# Power_Supply_and_Buttons.net
KiCad netlist of a schematic drawn in Altium Designer
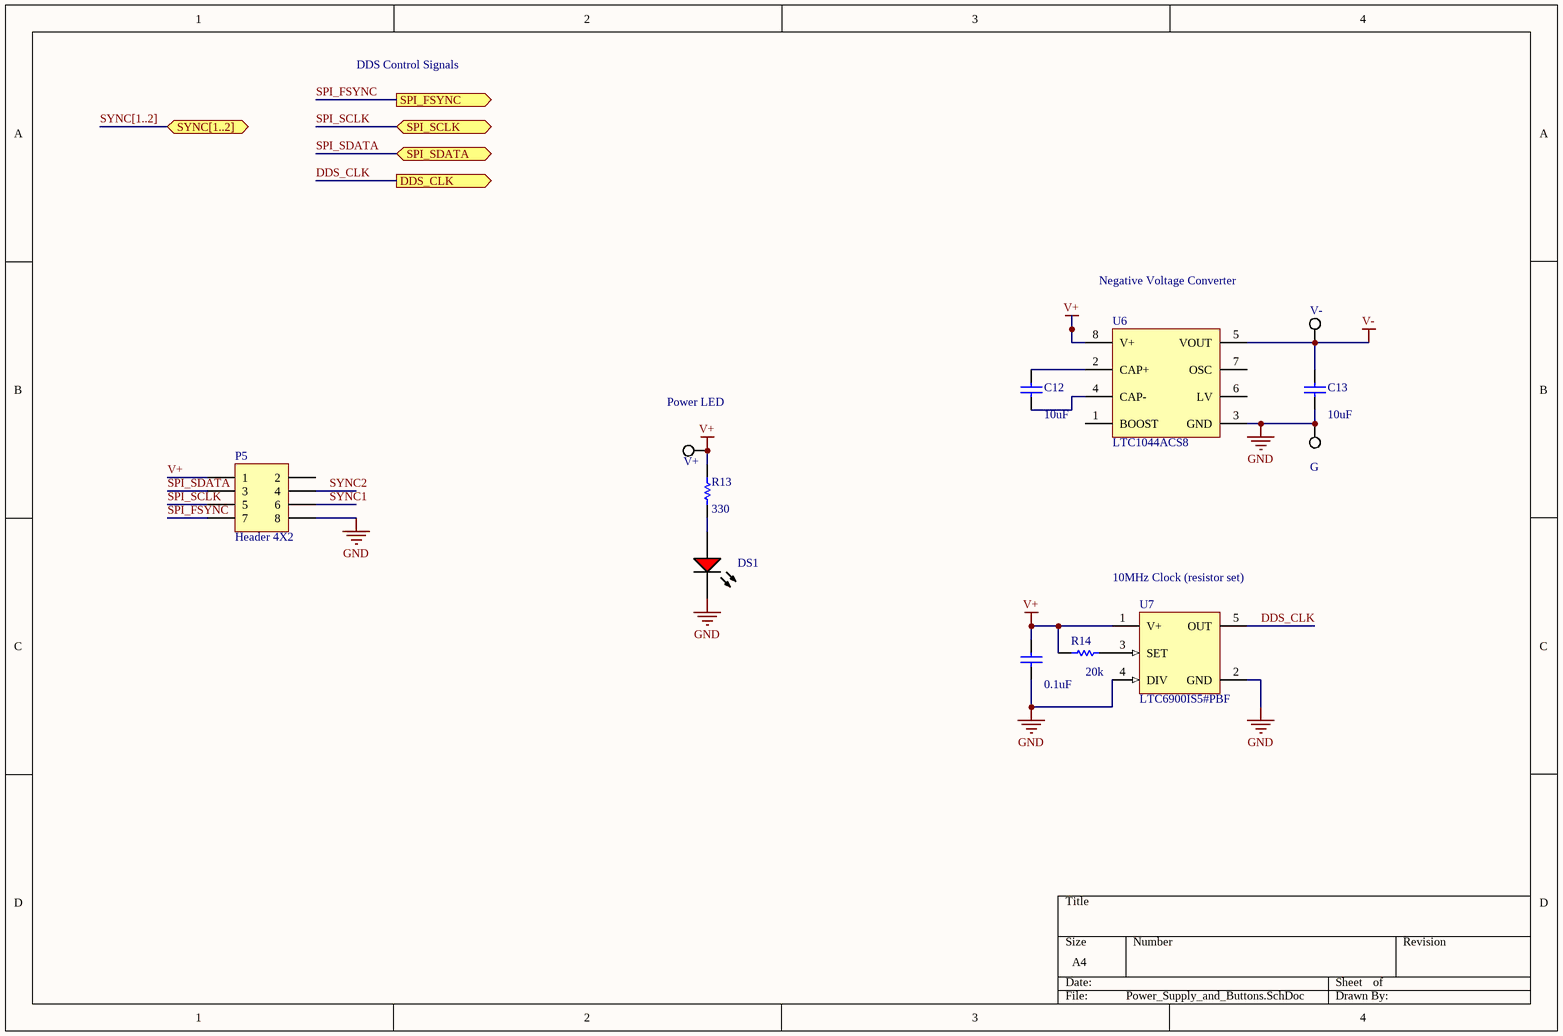
[diagram p0: Power_Supply_and_Buttons.SchDoc]

(export (version "E")
  (design (tool "Eeschema 10.0.6"))
  (components
    (comp (ref "C12")
      (value "10uF")
      (footprint "1608[0603]")
      (description "Capacitor (Semiconductor SIM Model)")
      (fields (field (name "PUBLISHER") "Altium Limited"))
      (libsource (lib "Miscellaneous Devices") (part "Cap Semi"))
    )
    (comp (ref "C13")
      (value "10uF")
      (footprint "1608[0603]")
      (description "Capacitor (Semiconductor SIM Model)")
      (fields (field (name "PUBLISHER") "Altium Limited"))
      (libsource (lib "Miscellaneous Devices") (part "Cap Semi"))
    )
    (comp (ref "C14")
      (value "0.1uF")
      (footprint "1608[0603]")
      (description "Capacitor (Semiconductor SIM Model)")
      (fields (field (name "PUBLISHER") "Altium Limited"))
      (libsource (lib "Miscellaneous Devices") (part "Cap Semi"))
    )
    (comp (ref "DS1")
      (value "TLMS1100-GS08")
      (footprint "VISH-TLMX1100_V")
      (description "LED, RED, 2.1 V, -40 to 100 degC, 2-Pin SMD (0603), RoHS, Tape and Reel")
      (fields (field (name "TOLERANCE") "5%"))
      (libsource (lib "Altium Content Vault") (part "CMP-1666-00027-1"))
    )
    (comp (ref "G")
      (value "TESTPOINT_WHITE")
      (footprint "TestPointVia")
      (libsource (lib "altium-import") (part "root_2_TESTPOINT_WHITE_"))
    )
    (comp (ref "P5")
      (value "Header 4X2")
      (footprint "HDR2X4")
      (description "Header, 4-Pin, Dual row")
      (fields (field (name "PUBLISHER") "Altium Limited"))
      (libsource (lib "Miscellaneous Connectors") (part "Header 4X2"))
    )
    (comp (ref "R13")
      (value "330")
      (footprint "6-0805_M")
      (description "Resistor")
      (fields (field (name "PUBLISHER") "Altium Limited"))
      (libsource (lib "Miscellaneous Devices") (part "Res1"))
    )
    (comp (ref "R14")
      (value "20k")
      (footprint "6-0805_M")
      (description "Resistor")
      (fields (field (name "PUBLISHER") "Altium Limited"))
      (libsource (lib "Miscellaneous Devices") (part "Res1"))
    )
    (comp (ref "U6")
      (value "LTC1044ACS8")
      (footprint "LT-S8-8_M")
      (description "12 V CMOS Voltage Converter, 8-pin SOIC (S8-8), 0 to 70 degC")
      (fields (field (name "MANUFACTURER") "Linear Technology"))
      (libsource (lib "Altium Content Vault") (part "LT-LTC104XX-8"))
    )
    (comp (ref "U7")
      (value "LTC6900IS5#PBF")
      (footprint "LT-TSOT-23-5_V")
      (fields (field (name "MANUFACTURER") "Linear Technology"))
      (libsource (lib "Altium Content Vault") (part "LT-LTC6900-TSOT-23-5"))
    )
    (comp (ref "V+")
      (value "TESTPOINT_WHITE")
      (footprint "TestPointVia")
      (libsource (lib "altium-import") (part "root_1_TESTPOINT_WHITE_"))
    )
    (comp (ref "V-")
      (value "TESTPOINT_WHITE")
      (footprint "TestPointVia")
      (libsource (lib "altium-import") (part "root_0_TESTPOINT_WHITE_"))
    )
  )
  (nets
    (net (code "1") (name "/DDS_CLK") (class "Default")
      (node (ref "U7") (pin "5") (pinfunction "OUT_5") (pintype "open_collector"))
    )
    (net (code "2") (name "/SPI_FSYNC") (class "Default")
      (node (ref "P5") (pin "7") (pinfunction "7_7") (pintype "passive"))
    )
    (net (code "3") (name "/SPI_SCLK") (class "Default")
      (node (ref "P5") (pin "5") (pinfunction "5_5") (pintype "passive"))
    )
    (net (code "4") (name "/SPI_SDATA") (class "Default")
      (node (ref "P5") (pin "3") (pinfunction "3_3") (pintype "passive"))
    )
    (net (code "5") (name "/SYNC1") (class "Default")
      (node (ref "P5") (pin "6") (pinfunction "6_6") (pintype "passive"))
    )
    (net (code "6") (name "/SYNC2") (class "Default")
      (node (ref "P5") (pin "4") (pinfunction "4_4") (pintype "passive"))
    )
    (net (code "8") (name "GND") (class "Default")
      (node (ref "C13") (pin "1") (pinfunction "1_1") (pintype "passive"))
      (node (ref "C14") (pin "1") (pinfunction "1_1") (pintype "passive"))
      (node (ref "DS1") (pin "2") (pinfunction "K_2") (pintype "passive"))
      (node (ref "G") (pin "1") (pinfunction "1_1") (pintype "passive"))
      (node (ref "P5") (pin "8") (pinfunction "8_8") (pintype "passive"))
      (node (ref "U6") (pin "3") (pinfunction "GND_3") (pintype "power_in"))
      (node (ref "U7") (pin "2") (pinfunction "GND_2") (pintype "power_in"))
      (node (ref "U7") (pin "4") (pinfunction "DIV_4") (pintype "input"))
    )
    (net (code "9") (name "Net-(DS1-A)") (class "Default")
      (node (ref "DS1") (pin "1") (pinfunction "A_1") (pintype "passive"))
      (node (ref "R13") (pin "1") (pinfunction "1_1") (pintype "passive"))
    )
    (net (code "10") (name "Net-(U6-CAP+)") (class "Default")
      (node (ref "C12") (pin "2") (pinfunction "2_2") (pintype "passive"))
      (node (ref "U6") (pin "2") (pinfunction "CAP+_2") (pintype "passive"))
    )
    (net (code "11") (name "Net-(U6-CAP-)") (class "Default")
      (node (ref "C12") (pin "1") (pinfunction "1_1") (pintype "passive"))
      (node (ref "U6") (pin "4") (pinfunction "CAP-_4") (pintype "passive"))
    )
    (net (code "12") (name "Net-(U7-SET)") (class "Default")
      (node (ref "R14") (pin "2") (pinfunction "2_2") (pintype "passive"))
      (node (ref "U7") (pin "3") (pinfunction "SET_3") (pintype "input"))
    )
    (net (code "13") (name "V+") (class "Default")
      (node (ref "C14") (pin "2") (pinfunction "2_2") (pintype "passive"))
      (node (ref "P5") (pin "1") (pinfunction "1_1") (pintype "passive"))
      (node (ref "R13") (pin "2") (pinfunction "2_2") (pintype "passive"))
      (node (ref "R14") (pin "1") (pinfunction "1_1") (pintype "passive"))
      (node (ref "U6") (pin "8") (pinfunction "V+_8") (pintype "power_in"))
      (node (ref "U7") (pin "1") (pinfunction "V+_1") (pintype "power_in"))
      (node (ref "V+") (pin "1") (pinfunction "1_1") (pintype "passive"))
    )
    (net (code "14") (name "V-") (class "Default")
      (node (ref "C13") (pin "2") (pinfunction "2_2") (pintype "passive"))
      (node (ref "U6") (pin "5") (pinfunction "VOUT_5") (pintype "power_in"))
      (node (ref "V-") (pin "1") (pinfunction "1_1") (pintype "passive"))
    )
    (net (code "15") (name "unconnected-(P5-Pad2)") (class "Default")
      (node (ref "P5") (pin "2") (pinfunction "2_2") (pintype "passive"))
    )
    (net (code "16") (name "unconnected-(U6-BOOST-Pad1)") (class "Default")
      (node (ref "U6") (pin "1") (pinfunction "BOOST_1") (pintype "passive"))
    )
    (net (code "17") (name "unconnected-(U6-LV-Pad6)") (class "Default")
      (node (ref "U6") (pin "6") (pinfunction "LV_6") (pintype "passive"))
    )
    (net (code "18") (name "unconnected-(U6-OSC-Pad7)") (class "Default")
      (node (ref "U6") (pin "7") (pinfunction "OSC_7") (pintype "passive"))
    )
  )
)
